# RoverWing-V1_5.net
KiCad netlist of a schematic drawn in EAGLE
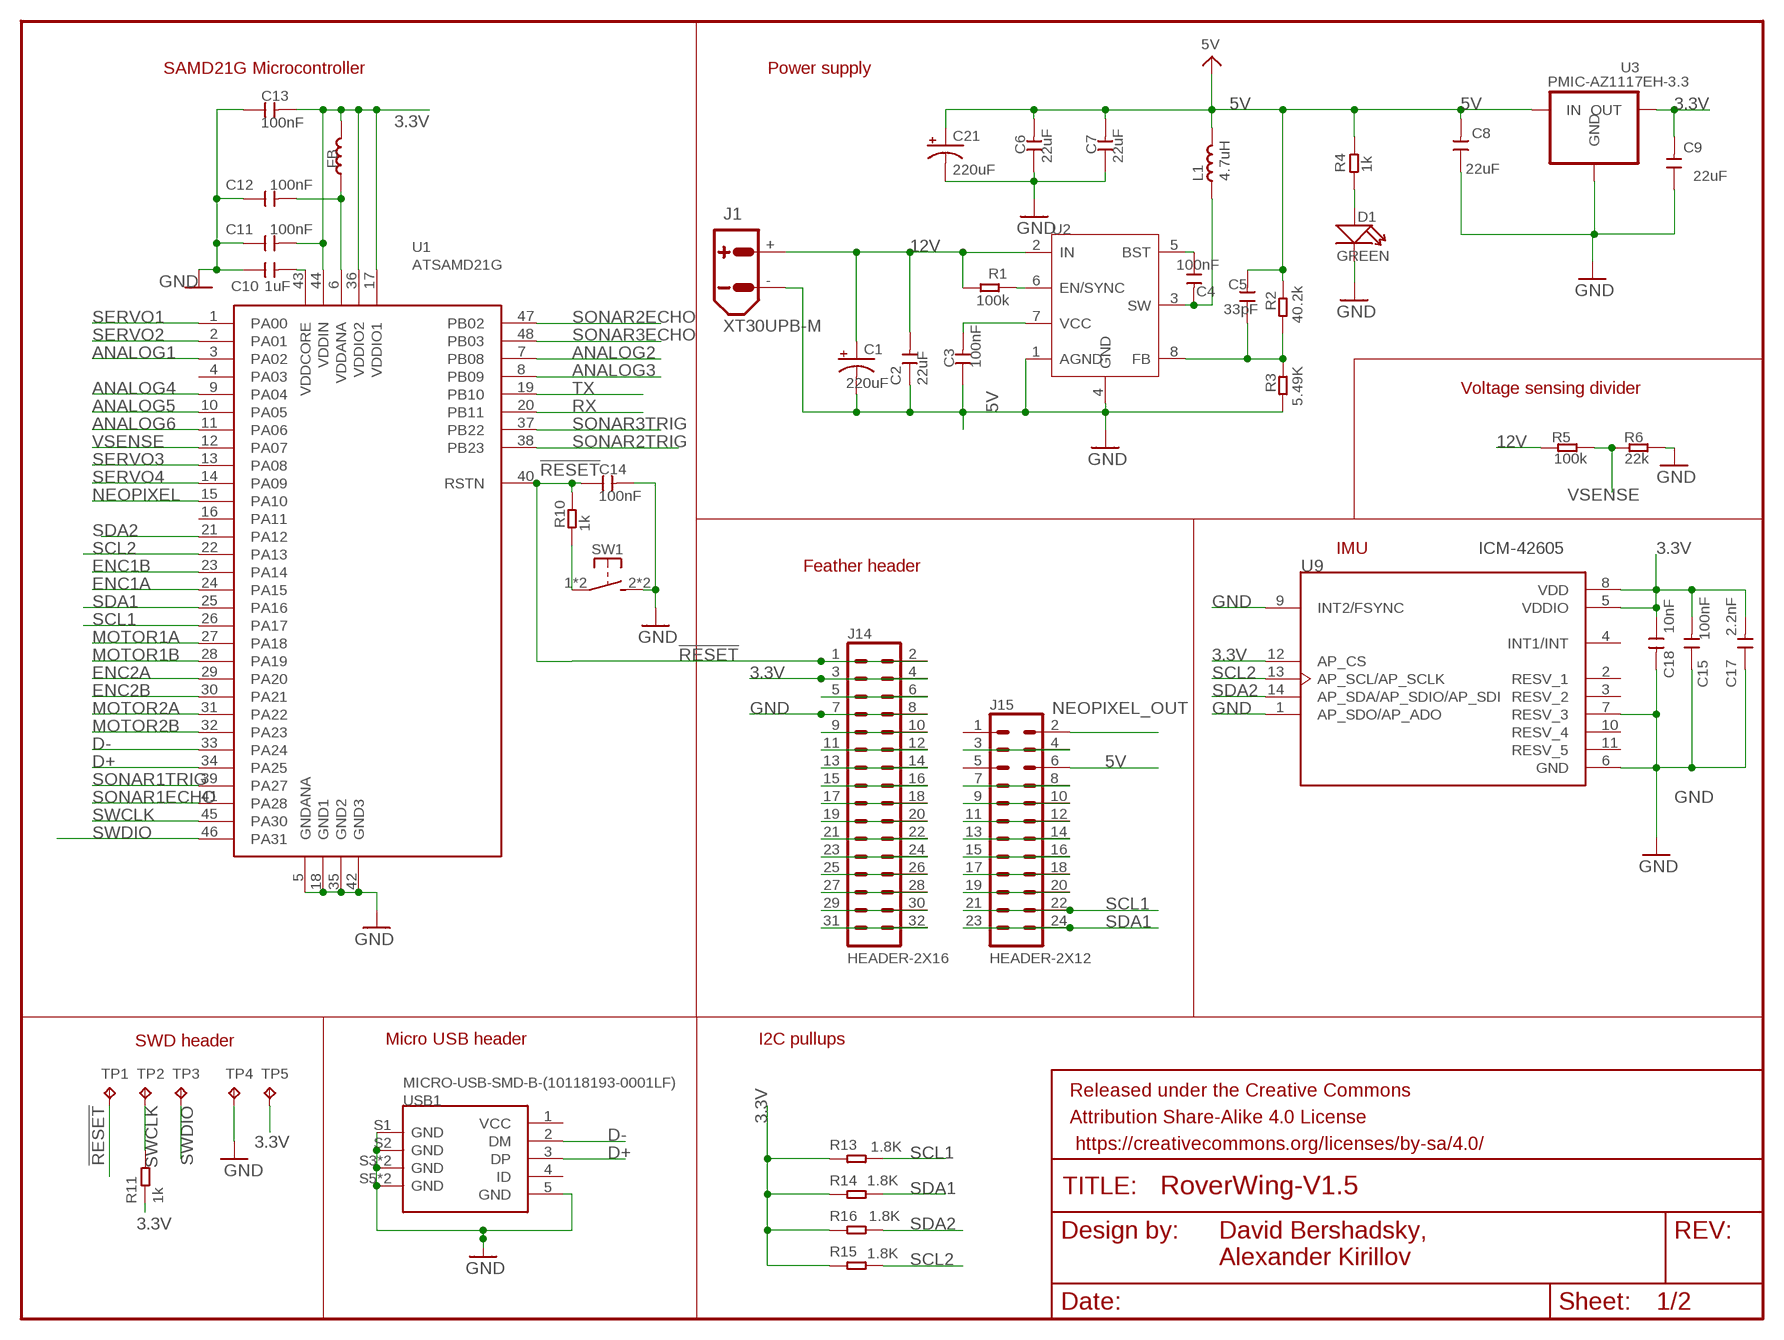
[diagram p0: schematic, sheet 1]
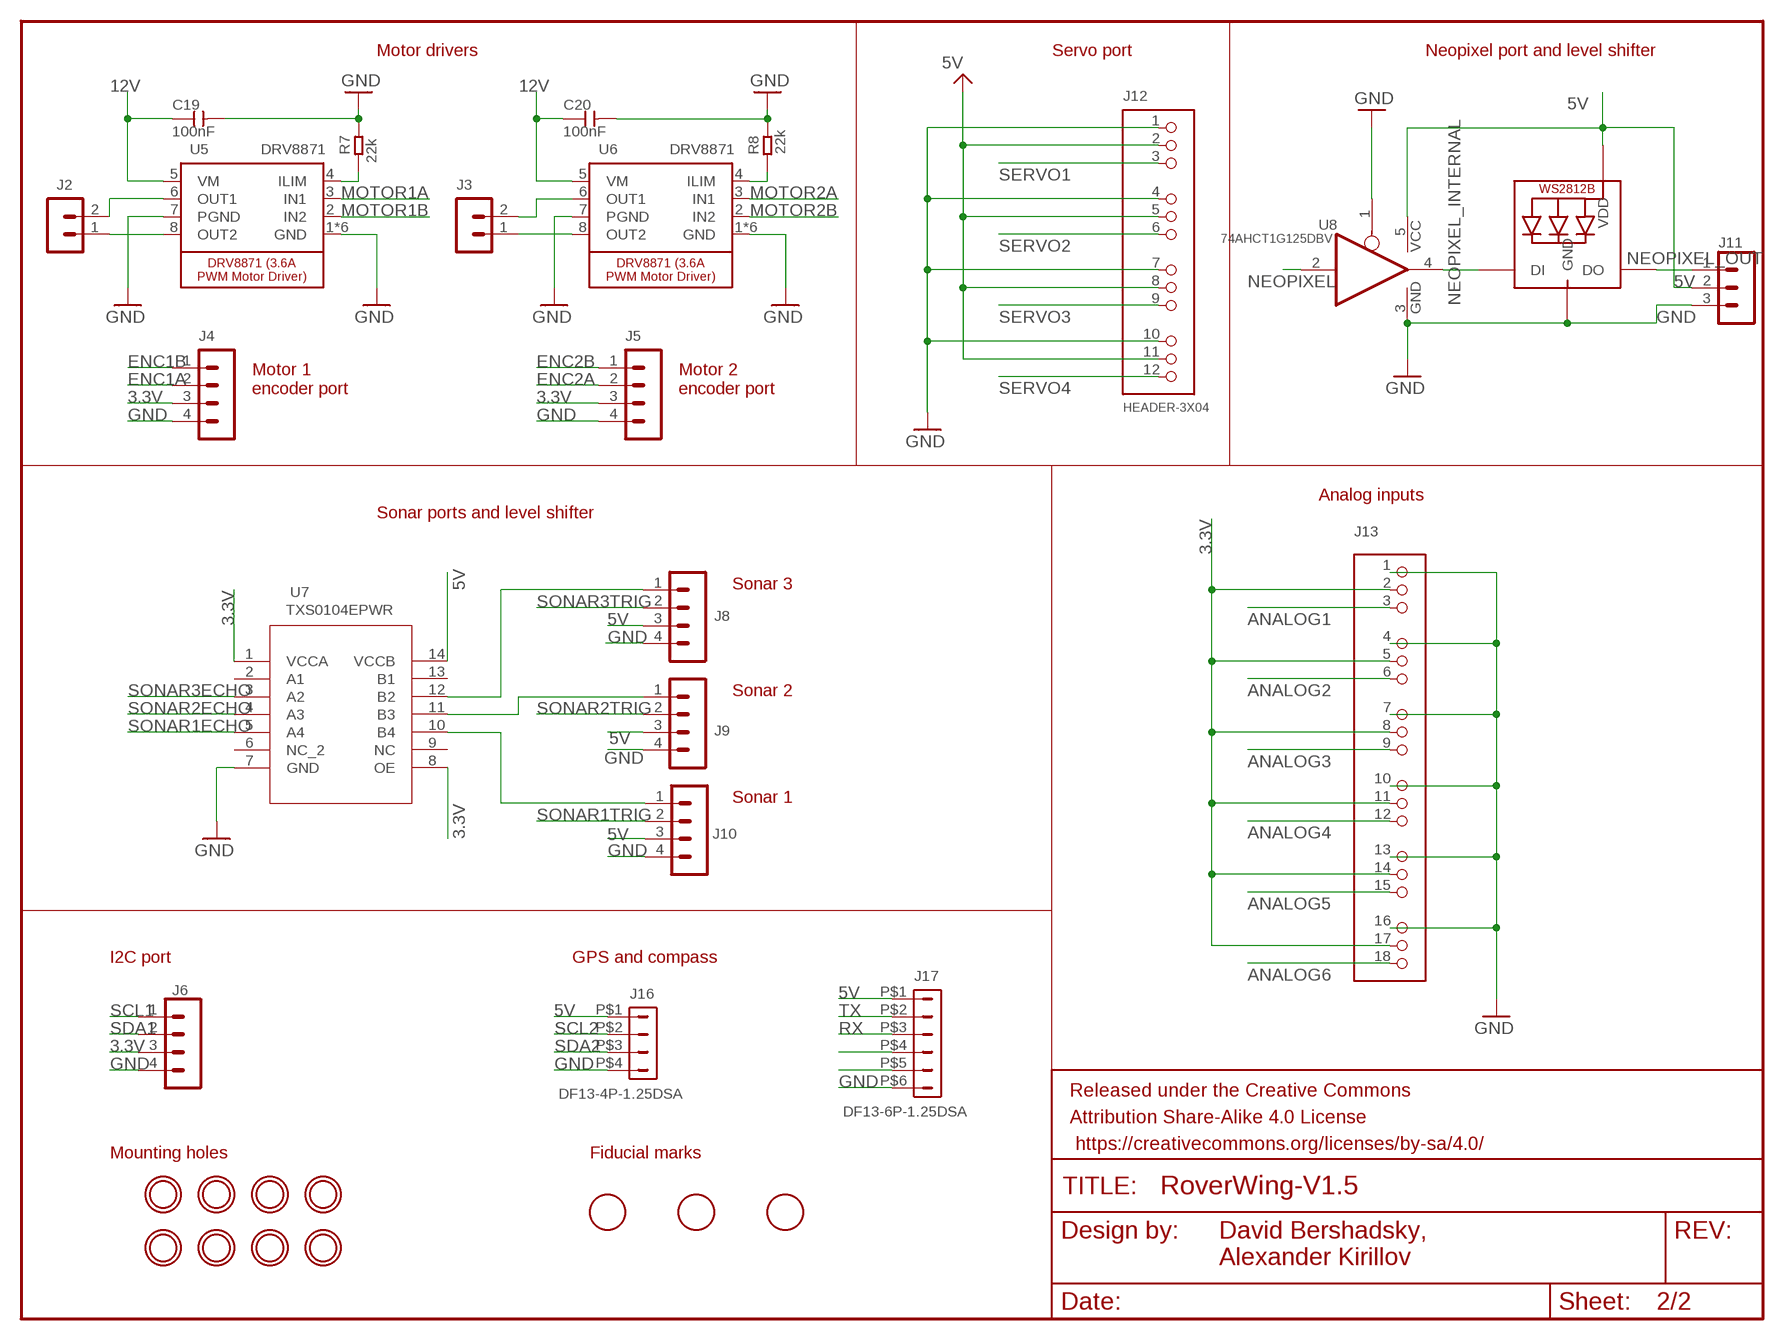
[diagram p1: schematic, sheet 2]

(export (version "E")
  (design (tool "Eeschema 10.0.6"))
  (components
    (comp (ref "C19")
      (value "100nF")
      (footprint "eagle-import:0805")
      (libsource (lib "eagle-import") (part "CAP-CERAMIC-SMD0805"))
    )
    (comp (ref "C20")
      (value "100nF")
      (footprint "eagle-import:0805")
      (libsource (lib "eagle-import") (part "CAP-CERAMIC-SMD0805"))
    )
    (comp (ref "D2")
      (value "WS2812B3535")
      (footprint "eagle-import:LED3535")
      (fields (field (name "MANUFACTURER") "Worldsemi") (field (name "PARTNO") "WS2812B-3535 "))
      (libsource (lib "eagle-import") (part "WS2812B3535"))
    )
    (comp (ref "FRAME1")
      (value "FRAME-LETTERNO_PACKAGE")
      (footprint "eagle-import:DUMMY")
      (libsource (lib "eagle-import") (part "FRAME-LETTERNO_PACKAGE"))
    )
    (comp (ref "J2")
      (value "HEADER-VH")
      (footprint "eagle-import:B2P-VH")
      (fields (field (name "PARTNO") "B2P-VH(LF)(SN)  "))
      (libsource (lib "eagle-import") (part "HEADER-VH"))
    )
    (comp (ref "J3")
      (value "HEADER-VH")
      (footprint "eagle-import:B2P-VH")
      (fields (field (name "PARTNO") "B2P-VH(LF)(SN)  "))
      (libsource (lib "eagle-import") (part "HEADER-VH"))
    )
    (comp (ref "J4")
      (value "HEADER-PH-4P")
      (footprint "eagle-import:B4B-PH-K")
      (fields (field (name "PARTNO") "B4B-PH-K-S(LF)(SN)"))
      (libsource (lib "eagle-import") (part "HEADER-PH-4P"))
    )
    (comp (ref "J5")
      (value "HEADER-PH-4P")
      (footprint "eagle-import:B4B-PH-K")
      (fields (field (name "PARTNO") "B4B-PH-K-S(LF)(SN)"))
      (libsource (lib "eagle-import") (part "HEADER-PH-4P"))
    )
    (comp (ref "J6")
      (value "HEADER-PH-4P")
      (footprint "eagle-import:B4B-PH-K")
      (fields (field (name "PARTNO") "B4B-PH-K-S(LF)(SN)"))
      (libsource (lib "eagle-import") (part "HEADER-PH-4P"))
    )
    (comp (ref "J8")
      (value "HEADER-PH-4P")
      (footprint "eagle-import:B4B-PH-K")
      (fields (field (name "PARTNO") "B4B-PH-K-S(LF)(SN)"))
      (libsource (lib "eagle-import") (part "HEADER-PH-4P"))
    )
    (comp (ref "J9")
      (value "HEADER-PH-4P")
      (footprint "eagle-import:B4B-PH-K")
      (fields (field (name "PARTNO") "B4B-PH-K-S(LF)(SN)"))
      (libsource (lib "eagle-import") (part "HEADER-PH-4P"))
    )
    (comp (ref "J10")
      (value "HEADER-PH-4P")
      (footprint "eagle-import:B4B-PH-K")
      (fields (field (name "PARTNO") "B4B-PH-K-S(LF)(SN)"))
      (libsource (lib "eagle-import") (part "HEADER-PH-4P"))
    )
    (comp (ref "J11")
      (value "HEADER-PH-3P")
      (footprint "eagle-import:B3B-PH-K")
      (fields (field (name "PARTNO") "B3B-PH-K-S(LF)(SN)"))
      (libsource (lib "eagle-import") (part "HEADER-PH-3P"))
    )
    (comp (ref "J12")
      (value "HEADER-3X04")
      (footprint "eagle-import:3X04")
      (libsource (lib "eagle-import") (part "HEADER-3X04"))
    )
    (comp (ref "J13")
      (value "HEADER-3X06\"")
      (footprint "eagle-import:3X06")
      (libsource (lib "eagle-import") (part "HEADER-3X06{dblquote}"))
    )
    (comp (ref "J16")
      (value "DF13-4P-1.25DSA")
      (footprint "eagle-import:DF13-4P-1.25DSA")
      (libsource (lib "eagle-import") (part "DF13-4P-1.25DSA"))
    )
    (comp (ref "J17")
      (value "DF13-6P-1.25DSA")
      (footprint "eagle-import:DF13-6P-1.25DSA")
      (libsource (lib "eagle-import") (part "DF13-6P-1.25DSA"))
    )
    (comp (ref "R7")
      (value "22k")
      (footprint "eagle-import:0805")
      (libsource (lib "eagle-import") (part "RES-SMD-0805"))
    )
    (comp (ref "R8")
      (value "22k")
      (footprint "eagle-import:0805")
      (libsource (lib "eagle-import") (part "RES-SMD-0805"))
    )
    (comp (ref "U$3")
      (value "MOUNTINGHOLE3.0_NPH")
      (footprint "eagle-import:MOUNTINGHOLE_3.0_NPH")
      (libsource (lib "eagle-import") (part "MOUNTINGHOLE3.0_NPH"))
    )
    (comp (ref "U$4")
      (value "MOUNTINGHOLE3.0_NPH")
      (footprint "eagle-import:MOUNTINGHOLE_3.0_NPH")
      (libsource (lib "eagle-import") (part "MOUNTINGHOLE3.0_NPH"))
    )
    (comp (ref "U$11")
      (value "FIDUCIAL")
      (footprint "eagle-import:FIDUCIAL_1MM")
      (libsource (lib "eagle-import") (part "FIDUCIAL"))
    )
    (comp (ref "U$13")
      (value "FIDUCIAL")
      (footprint "eagle-import:FIDUCIAL_1MM")
      (libsource (lib "eagle-import") (part "FIDUCIAL"))
    )
    (comp (ref "U$14")
      (value "MOUNTINGHOLE3.0_NPH")
      (footprint "eagle-import:MOUNTINGHOLE_3.0_NPH")
      (libsource (lib "eagle-import") (part "MOUNTINGHOLE3.0_NPH"))
    )
    (comp (ref "U$15")
      (value "MOUNTINGHOLE3.0_NPH")
      (footprint "eagle-import:MOUNTINGHOLE_3.0_NPH")
      (libsource (lib "eagle-import") (part "MOUNTINGHOLE3.0_NPH"))
    )
    (comp (ref "U$17")
      (value "FIDUCIAL")
      (footprint "eagle-import:FIDUCIAL_1MM")
      (libsource (lib "eagle-import") (part "FIDUCIAL"))
    )
    (comp (ref "U$24")
      (value "MOUNTINGHOLE3.0_NPH")
      (footprint "eagle-import:MOUNTINGHOLE_3.0_NPH")
      (libsource (lib "eagle-import") (part "MOUNTINGHOLE3.0_NPH"))
    )
    (comp (ref "U$25")
      (value "MOUNTINGHOLE3.0_NPH")
      (footprint "eagle-import:MOUNTINGHOLE_3.0_NPH")
      (libsource (lib "eagle-import") (part "MOUNTINGHOLE3.0_NPH"))
    )
    (comp (ref "U$26")
      (value "MOUNTINGHOLE3.0_NPH")
      (footprint "eagle-import:MOUNTINGHOLE_3.0_NPH")
      (libsource (lib "eagle-import") (part "MOUNTINGHOLE3.0_NPH"))
    )
    (comp (ref "U$27")
      (value "MOUNTINGHOLE3.0_NPH")
      (footprint "eagle-import:MOUNTINGHOLE_3.0_NPH")
      (libsource (lib "eagle-import") (part "MOUNTINGHOLE3.0_NPH"))
    )
    (comp (ref "U5")
      (value "DRV8871")
      (footprint "eagle-import:HSOP8")
      (fields (field (name "MANUFACTURER") "TEXAS INSTRUMENTS") (field (name "PARTNO") "DRV8871DDAR"))
      (libsource (lib "eagle-import") (part "DRV8871"))
    )
    (comp (ref "U6")
      (value "DRV8871")
      (footprint "eagle-import:HSOP8")
      (fields (field (name "MANUFACTURER") "TEXAS INSTRUMENTS") (field (name "PARTNO") "DRV8871DDAR"))
      (libsource (lib "eagle-import") (part "DRV8871"))
    )
    (comp (ref "U7")
      (value "TXS0104EPWR")
      (footprint "eagle-import:PW14")
      (fields (field (name "MANUFACTURER") "Texas Instruments"))
      (libsource (lib "eagle-import") (part "TXS0104EPWR"))
    )
    (comp (ref "U8")
      (value "74AHCT1G125DBV")
      (footprint "eagle-import:SOT23-5")
      (fields (field (name "PARTNO") "SN74AHCT1G125DBVR"))
      (libsource (lib "eagle-import") (part "741G125DBVAHCT"))
    )
    (comp (ref "C1")
      (value "220uF")
      (footprint "eagle-import:CAP-8X10.5")
      (libsource (lib "eagle-import") (part "CAP-POL-SMD-8X10.5"))
    )
    (comp (ref "C2")
      (value "22uF")
      (footprint "eagle-import:0805")
      (libsource (lib "eagle-import") (part "CAP-CERAMIC-SMD0805"))
    )
    (comp (ref "C3")
      (value "100nF")
      (footprint "eagle-import:0805")
      (libsource (lib "eagle-import") (part "CAP-CERAMIC-SMD0805"))
    )
    (comp (ref "C4")
      (value "100nF")
      (footprint "eagle-import:0805")
      (libsource (lib "eagle-import") (part "CAP-CERAMIC-SMD0805"))
    )
    (comp (ref "C5")
      (value "33pF")
      (footprint "eagle-import:0805")
      (libsource (lib "eagle-import") (part "CAP-CERAMIC-SMD0805"))
    )
    (comp (ref "C6")
      (value "22uF")
      (footprint "eagle-import:0805")
      (libsource (lib "eagle-import") (part "CAP-CERAMIC-SMD0805"))
    )
    (comp (ref "C7")
      (value "22uF")
      (footprint "eagle-import:0805")
      (libsource (lib "eagle-import") (part "CAP-CERAMIC-SMD0805"))
    )
    (comp (ref "C8")
      (value "22uF")
      (footprint "eagle-import:0805")
      (libsource (lib "eagle-import") (part "CAP-CERAMIC-SMD0805"))
    )
    (comp (ref "C9")
      (value "22uF")
      (footprint "eagle-import:0805")
      (libsource (lib "eagle-import") (part "CAP-CERAMIC-SMD0805"))
    )
    (comp (ref "C10")
      (value "1uF")
      (footprint "eagle-import:0805")
      (libsource (lib "eagle-import") (part "CAP-CERAMIC-SMD0805"))
    )
    (comp (ref "C11")
      (value "100nF")
      (footprint "eagle-import:0805")
      (libsource (lib "eagle-import") (part "CAP-CERAMIC-SMD0805"))
    )
    (comp (ref "C12")
      (value "100nF")
      (footprint "eagle-import:0805")
      (libsource (lib "eagle-import") (part "CAP-CERAMIC-SMD0805"))
    )
    (comp (ref "C13")
      (value "100nF")
      (footprint "eagle-import:0805")
      (libsource (lib "eagle-import") (part "CAP-CERAMIC-SMD0805"))
    )
    (comp (ref "C14")
      (value "100nF")
      (footprint "eagle-import:0805")
      (libsource (lib "eagle-import") (part "CAP-CERAMIC-SMD0805"))
    )
    (comp (ref "C15")
      (value "100nF")
      (footprint "eagle-import:0805")
      (libsource (lib "eagle-import") (part "CAP-CERAMIC-SMD0805"))
    )
    (comp (ref "C17")
      (value "2.2nF")
      (footprint "eagle-import:0805")
      (libsource (lib "eagle-import") (part "CAP-CERAMIC-SMD0805"))
    )
    (comp (ref "C18")
      (value "10nF")
      (footprint "eagle-import:0805")
      (libsource (lib "eagle-import") (part "CAP-CERAMIC-SMD0805"))
    )
    (comp (ref "C21")
      (value "220uF")
      (footprint "eagle-import:CAP-6.3X5.4")
      (fields (field (name "PARTNO") "CS1E470M-CRE54 "))
      (libsource (lib "eagle-import") (part "CAP-POL-SMD-6.3X5.4"))
    )
    (comp (ref "D1")
      (value "GREEN")
      (footprint "eagle-import:LED-0805")
      (libsource (lib "eagle-import") (part "SMD-LED-0805"))
    )
    (comp (ref "FB")
      (value "330R-1500MA")
      (footprint "eagle-import:0805")
      (fields (field (name "PARTNO") "BLM21PG331SN1D"))
      (libsource (lib "eagle-import") (part "SMD-FERRITE-BEAD-330R-1500MA(0805)"))
    )
    (comp (ref "FRAME2")
      (value "FRAME-LETTERNO_PACKAGE")
      (footprint "eagle-import:DUMMY")
      (libsource (lib "eagle-import") (part "FRAME-LETTERNO_PACKAGE"))
    )
    (comp (ref "J1")
      (value "XT30UPB-M")
      (footprint "eagle-import:XT30UPB-M")
      (libsource (lib "eagle-import") (part "XT30UPB-M"))
    )
    (comp (ref "J14")
      (value "HEADER-2X16")
      (footprint "eagle-import:2X16")
      (libsource (lib "eagle-import") (part "HEADER-2X16"))
    )
    (comp (ref "J15")
      (value "HEADER-2X12")
      (footprint "eagle-import:2X12")
      (libsource (lib "eagle-import") (part "HEADER-2X12"))
    )
    (comp (ref "L1")
      (value "4.7uH")
      (footprint "eagle-import:IND_TDK_7.1X6.5")
      (fields (field (name "MANUFACTURER") "TDK") (field (name "PARTNO") "SPM6530T-4R7M "))
      (libsource (lib "eagle-import") (part "IND-TDK-SPM6530T"))
    )
    (comp (ref "R1")
      (value "100k")
      (footprint "eagle-import:0805")
      (libsource (lib "eagle-import") (part "RES-SMD-0805"))
    )
    (comp (ref "R2")
      (value "40.2k")
      (footprint "eagle-import:0805")
      (libsource (lib "eagle-import") (part "RES-SMD-0805"))
    )
    (comp (ref "R3")
      (value "5.49K")
      (footprint "eagle-import:0805")
      (libsource (lib "eagle-import") (part "RES-SMD-0805"))
    )
    (comp (ref "R4")
      (value "1k")
      (footprint "eagle-import:0805")
      (libsource (lib "eagle-import") (part "RES-SMD-0805"))
    )
    (comp (ref "R5")
      (value "100k")
      (footprint "eagle-import:0805")
      (libsource (lib "eagle-import") (part "RES-SMD-0805"))
    )
    (comp (ref "R6")
      (value "22k")
      (footprint "eagle-import:0805")
      (libsource (lib "eagle-import") (part "RES-SMD-0805"))
    )
    (comp (ref "R10")
      (value "1k")
      (footprint "eagle-import:0805")
      (libsource (lib "eagle-import") (part "RES-SMD-0805"))
    )
    (comp (ref "R11")
      (value "1k")
      (footprint "eagle-import:0805")
      (libsource (lib "eagle-import") (part "RES-SMD-0805"))
    )
    (comp (ref "R13")
      (value "1.8K")
      (footprint "eagle-import:R0603")
      (fields (field (name "MPN") "RC0603FR-071K8L"))
      (libsource (lib "eagle-import") (part "SMD-RES-1.8K-1%-1/10W(0603)"))
    )
    (comp (ref "R14")
      (value "1.8K")
      (footprint "eagle-import:R0603")
      (fields (field (name "MPN") "RC0603FR-071K8L"))
      (libsource (lib "eagle-import") (part "SMD-RES-1.8K-1%-1/10W(0603)"))
    )
    (comp (ref "R15")
      (value "1.8K")
      (footprint "eagle-import:R0603")
      (fields (field (name "MPN") "RC0603FR-071K8L"))
      (libsource (lib "eagle-import") (part "SMD-RES-1.8K-1%-1/10W(0603)"))
    )
    (comp (ref "R16")
      (value "1.8K")
      (footprint "eagle-import:R0603")
      (fields (field (name "MPN") "RC0603FR-071K8L"))
      (libsource (lib "eagle-import") (part "SMD-RES-1.8K-1%-1/10W(0603)"))
    )
    (comp (ref "SW1")
      (value "SW-TACTILE-4.5X4.5_SMD")
      (footprint "eagle-import:TL3305")
      (fields (field (name "MANUFACTURER") "BRIGHT") (field (name "PARTNO") "TSA453G38-250 "))
      (libsource (lib "eagle-import") (part "SW-TACTILE-4.5X4.5_SMD"))
    )
    (comp (ref "TP1")
      (value "TPTP15R")
      (footprint "eagle-import:TP15R")
      (libsource (lib "eagle-import") (part "TPTP15R"))
    )
    (comp (ref "TP2")
      (value "TPTP15R")
      (footprint "eagle-import:TP15R")
      (libsource (lib "eagle-import") (part "TPTP15R"))
    )
    (comp (ref "TP3")
      (value "TPTP15R")
      (footprint "eagle-import:TP15R")
      (libsource (lib "eagle-import") (part "TPTP15R"))
    )
    (comp (ref "TP4")
      (value "TPTP15R")
      (footprint "eagle-import:TP15R")
      (libsource (lib "eagle-import") (part "TPTP15R"))
    )
    (comp (ref "TP5")
      (value "TPTP15R")
      (footprint "eagle-import:TP15R")
      (libsource (lib "eagle-import") (part "TPTP15R"))
    )
    (comp (ref "U1")
      (value "ATSAMD21G")
      (footprint "eagle-import:TQFP-48-EDITED")
      (fields (field (name "MANUFACTURER") "Microchip Technology") (field (name "PARTNO") "ATSAMD21G18A-AU"))
      (libsource (lib "eagle-import") (part "ATSAMD21G"))
    )
    (comp (ref "U2")
      (value "MP2225")
      (footprint "eagle-import:SOT-23-8")
      (fields (field (name "MANUFACTURER") "Monolithic Power Systems") (field (name "PARTNO") "MP2225GJ"))
      (libsource (lib "eagle-import") (part "PMIC-MP2225"))
    )
    (comp (ref "U3")
      (value "PMIC-AZ1117EH-3.3")
      (footprint "eagle-import:SOT223")
      (fields (field (name "PARTNO") "AZ1117EH-3.3TRG1"))
      (libsource (lib "eagle-import") (part "PMIC-AZ1117EH-3.3"))
    )
    (comp (ref "U9")
      (value "ICM-42605")
      (footprint "eagle-import:PQFN50P300X250X97-14N")
      (fields (field (name "DIGI-KEY_PART_NUMBER") "1428-1152-1-ND") (field (name "MF") "TDK InvenSense"))
      (libsource (lib "eagle-import") (part "ICM-42605"))
    )
    (comp (ref "USB1")
      (value "MICRO-USB-SMD-B-(10118193-0001LF)")
      (footprint "eagle-import:MICRO-USB5+6P-SMD-0.65-B")
      (fields (field (name "MANUFACTURER") "Amphenol ICC") (field (name "PARTNO") "10118193-0001LF"))
      (libsource (lib "eagle-import") (part "MICRO-USB-SMD-B-(10118193-0001LF)"))
    )
  )
  (nets
    (net (code "1") (name "3.3V") (class "Default")
      (node (ref "C11") (pin "2") (pinfunction "2_2") (pintype "passive"))
      (node (ref "C13") (pin "2") (pinfunction "2_2") (pintype "passive"))
      (node (ref "C15") (pin "2") (pinfunction "2_2") (pintype "passive"))
      (node (ref "C17") (pin "2") (pinfunction "2_2") (pintype "passive"))
      (node (ref "C18") (pin "1") (pinfunction "1_1") (pintype "passive"))
      (node (ref "C9") (pin "2") (pinfunction "2_2") (pintype "passive"))
      (node (ref "FB") (pin "2") (pinfunction "2_2") (pintype "passive"))
      (node (ref "J13") (pin "11") (pinfunction "11_11") (pintype "passive"))
      (node (ref "J13") (pin "14") (pinfunction "14_14") (pintype "passive"))
      (node (ref "J13") (pin "17") (pinfunction "17_17") (pintype "passive"))
      (node (ref "J13") (pin "2") (pinfunction "2_2") (pintype "passive"))
      (node (ref "J13") (pin "5") (pinfunction "5_5") (pintype "passive"))
      (node (ref "J13") (pin "8") (pinfunction "8_8") (pintype "passive"))
      (node (ref "J14") (pin "3") (pinfunction "3_3") (pintype "passive"))
      (node (ref "J14") (pin "4") (pinfunction "4_4") (pintype "passive"))
      (node (ref "J4") (pin "3") (pinfunction "3_3") (pintype "passive"))
      (node (ref "J5") (pin "3") (pinfunction "3_3") (pintype "passive"))
      (node (ref "J6") (pin "3") (pinfunction "3_3") (pintype "passive"))
      (node (ref "R11") (pin "1") (pinfunction "1_1") (pintype "passive"))
      (node (ref "R13") (pin "1") (pinfunction "1_1") (pintype "passive"))
      (node (ref "R14") (pin "1") (pinfunction "1_1") (pintype "passive"))
      (node (ref "R15") (pin "1") (pinfunction "1_1") (pintype "passive"))
      (node (ref "R16") (pin "1") (pinfunction "1_1") (pintype "passive"))
      (node (ref "TP5") (pin "TP") (pinfunction "TP_TP") (pintype "input"))
      (node (ref "U1") (pin "17") (pinfunction "VDDIO1_17") (pintype "power_in"))
      (node (ref "U1") (pin "36") (pinfunction "VDDIO2_36") (pintype "power_in"))
      (node (ref "U1") (pin "44") (pinfunction "VDDIN_44") (pintype "power_in"))
      (node (ref "U3") (pin "2") (pinfunction "OUT_2") (pintype "output"))
      (node (ref "U3") (pin "4") (pinfunction "OUT_4") (pintype "output"))
      (node (ref "U7") (pin "1") (pinfunction "VCCA_1") (pintype "power_in"))
      (node (ref "U7") (pin "8") (pinfunction "OE_8") (pintype "output"))
      (node (ref "U9") (pin "12") (pinfunction "AP_CS_12") (pintype "input"))
      (node (ref "U9") (pin "5") (pinfunction "VDDIO_5") (pintype "power_in"))
      (node (ref "U9") (pin "8") (pinfunction "VDD_8") (pintype "power_in"))
    )
    (net (code "2") (name "5V") (class "Default")
      (node (ref "C21") (pin "+") (pinfunction "+_+") (pintype "passive"))
      (node (ref "C5") (pin "2") (pinfunction "2_2") (pintype "passive"))
      (node (ref "C6") (pin "2") (pinfunction "2_2") (pintype "passive"))
      (node (ref "C7") (pin "2") (pinfunction "2_2") (pintype "passive"))
      (node (ref "C8") (pin "2") (pinfunction "2_2") (pintype "passive"))
      (node (ref "D2") (pin "3") (pinfunction "VDD_3") (pintype "power_in"))
      (node (ref "J10") (pin "3") (pinfunction "3_3") (pintype "passive"))
      (node (ref "J11") (pin "2") (pinfunction "2_2") (pintype "passive"))
      (node (ref "J12") (pin "11") (pinfunction "11_11") (pintype "passive"))
      (node (ref "J12") (pin "2") (pinfunction "2_2") (pintype "passive"))
      (node (ref "J12") (pin "5") (pinfunction "5_5") (pintype "passive"))
      (node (ref "J12") (pin "8") (pinfunction "8_8") (pintype "passive"))
      (node (ref "J15") (pin "6") (pinfunction "6_6") (pintype "passive"))
      (node (ref "J16") (pin "P$1") (pinfunction "1_P$1") (pintype "passive"))
      (node (ref "J17") (pin "P$1") (pinfunction "1_P$1") (pintype "passive"))
      (node (ref "J8") (pin "3") (pinfunction "3_3") (pintype "passive"))
      (node (ref "J9") (pin "3") (pinfunction "3_3") (pintype "passive"))
      (node (ref "L1") (pin "2") (pinfunction "2_2") (pintype "passive"))
      (node (ref "R2") (pin "1") (pinfunction "1_1") (pintype "passive"))
      (node (ref "R4") (pin "2") (pinfunction "2_2") (pintype "passive"))
      (node (ref "U3") (pin "3") (pinfunction "IN_3") (pintype "input"))
      (node (ref "U7") (pin "14") (pinfunction "VCCB_14") (pintype "power_in"))
      (node (ref "U8") (pin "5") (pinfunction "VCC_5") (pintype "power_in"))
    )
    (net (code "3") (name "12V") (class "Default")
      (node (ref "C1") (pin "+") (pinfunction "+_+") (pintype "passive"))
      (node (ref "C19") (pin "1") (pinfunction "1_1") (pintype "passive"))
      (node (ref "C2") (pin "2") (pinfunction "2_2") (pintype "passive"))
      (node (ref "C20") (pin "1") (pinfunction "1_1") (pintype "passive"))
      (node (ref "J1") (pin "+") (pinfunction "+_+") (pintype "power_in"))
      (node (ref "R1") (pin "2") (pinfunction "2_2") (pintype "passive"))
      (node (ref "R5") (pin "2") (pinfunction "2_2") (pintype "passive"))
      (node (ref "U2") (pin "2") (pinfunction "IN_2") (pintype "bidirectional"))
      (node (ref "U5") (pin "5") (pinfunction "VM_5") (pintype "power_in"))
      (node (ref "U6") (pin "5") (pinfunction "VM_5") (pintype "power_in"))
    )
    (net (code "4") (name "ANALOG1") (class "Default")
      (node (ref "J13") (pin "3") (pinfunction "3_3") (pintype "passive"))
      (node (ref "U1") (pin "3") (pinfunction "PA02_3") (pintype "bidirectional"))
    )
    (net (code "5") (name "ANALOG2") (class "Default")
      (node (ref "J13") (pin "6") (pinfunction "6_6") (pintype "passive"))
      (node (ref "U1") (pin "7") (pinfunction "PB08_7") (pintype "bidirectional"))
    )
    (net (code "6") (name "ANALOG3") (class "Default")
      (node (ref "J13") (pin "9") (pinfunction "9_9") (pintype "passive"))
      (node (ref "U1") (pin "8") (pinfunction "PB09_8") (pintype "bidirectional"))
    )
    (net (code "7") (name "ANALOG4") (class "Default")
      (node (ref "J13") (pin "12") (pinfunction "12_12") (pintype "passive"))
      (node (ref "U1") (pin "9") (pinfunction "PA04_9") (pintype "bidirectional"))
    )
    (net (code "8") (name "ANALOG5") (class "Default")
      (node (ref "J13") (pin "15") (pinfunction "15_15") (pintype "passive"))
      (node (ref "U1") (pin "10") (pinfunction "PA05_10") (pintype "bidirectional"))
    )
    (net (code "9") (name "ANALOG6") (class "Default")
      (node (ref "J13") (pin "18") (pinfunction "18_18") (pintype "passive"))
      (node (ref "U1") (pin "11") (pinfunction "PA06_11") (pintype "bidirectional"))
    )
    (net (code "10") (name "D+") (class "Default")
      (node (ref "U1") (pin "34") (pinfunction "PA25_34") (pintype "bidirectional"))
      (node (ref "USB1") (pin "3") (pinfunction "DP_3") (pintype "bidirectional"))
    )
    (net (code "11") (name "D-") (class "Default")
      (node (ref "U1") (pin "33") (pinfunction "PA24_33") (pintype "bidirectional"))
      (node (ref "USB1") (pin "2") (pinfunction "DM_2") (pintype "bidirectional"))
    )
    (net (code "12") (name "ENC1A") (class "Default")
      (node (ref "J4") (pin "2") (pinfunction "2_2") (pintype "passive"))
      (node (ref "U1") (pin "24") (pinfunction "PA15_24") (pintype "bidirectional"))
    )
    (net (code "13") (name "ENC1B") (class "Default")
      (node (ref "J4") (pin "1") (pinfunction "1_1") (pintype "passive"))
      (node (ref "U1") (pin "23") (pinfunction "PA14_23") (pintype "bidirectional"))
    )
    (net (code "14") (name "ENC2A") (class "Default")
      (node (ref "J5") (pin "2") (pinfunction "2_2") (pintype "passive"))
      (node (ref "U1") (pin "29") (pinfunction "PA20_29") (pintype "bidirectional"))
    )
    (net (code "15") (name "ENC2B") (class "Default")
      (node (ref "J5") (pin "1") (pinfunction "1_1") (pintype "passive"))
      (node (ref "U1") (pin "30") (pinfunction "PA21_30") (pintype "bidirectional"))
    )
    (net (code "16") (name "GND") (class "Default")
      (node (ref "C1") (pin "-") (pinfunction "-_-") (pintype "passive"))
      (node (ref "C10") (pin "1") (pinfunction "1_1") (pintype "passive"))
      (node (ref "C11") (pin "1") (pinfunction "1_1") (pintype "passive"))
      (node (ref "C12") (pin "1") (pinfunction "1_1") (pintype "passive"))
      (node (ref "C13") (pin "1") (pinfunction "1_1") (pintype "passive"))
      (node (ref "C14") (pin "2") (pinfunction "2_2") (pintype "passive"))
      (node (ref "C15") (pin "1") (pinfunction "1_1") (pintype "passive"))
      (node (ref "C17") (pin "1") (pinfunction "1_1") (pintype "passive"))
      (node (ref "C18") (pin "2") (pinfunction "2_2") (pintype "passive"))
      (node (ref "C19") (pin "2") (pinfunction "2_2") (pintype "passive"))
      (node (ref "C2") (pin "1") (pinfunction "1_1") (pintype "passive"))
      (node (ref "C20") (pin "2") (pinfunction "2_2") (pintype "passive"))
      (node (ref "C21") (pin "-") (pinfunction "-_-") (pintype "passive"))
      (node (ref "C3") (pin "1") (pinfunction "1_1") (pintype "passive"))
      (node (ref "C6") (pin "1") (pinfunction "1_1") (pintype "passive"))
      (node (ref "C7") (pin "1") (pinfunction "1_1") (pintype "passive"))
      (node (ref "C8") (pin "1") (pinfunction "1_1") (pintype "passive"))
      (node (ref "C9") (pin "1") (pinfunction "1_1") (pintype "passive"))
      (node (ref "D1") (pin "-") (pinfunction "-_-") (pintype "passive"))
      (node (ref "D2") (pin "1") (pinfunction "GND_1") (pintype "power_in"))
      (node (ref "J1") (pin "-") (pinfunction "-_-") (pintype "power_in"))
      (node (ref "J10") (pin "4") (pinfunction "4_4") (pintype "passive"))
      (node (ref "J11") (pin "3") (pinfunction "3_3") (pintype "passive"))
      (node (ref "J12") (pin "1") (pinfunction "1_1") (pintype "passive"))
      (node (ref "J12") (pin "10") (pinfunction "10_10") (pintype "passive"))
      (node (ref "J12") (pin "4") (pinfunction "4_4") (pintype "passive"))
      (node (ref "J12") (pin "7") (pinfunction "7_7") (pintype "passive"))
      (node (ref "J13") (pin "1") (pinfunction "1_1") (pintype "passive"))
      (node (ref "J13") (pin "10") (pinfunction "10_10") (pintype "passive"))
      (node (ref "J13") (pin "13") (pinfunction "13_13") (pintype "passive"))
      (node (ref "J13") (pin "16") (pinfunction "16_16") (pintype "passive"))
      (node (ref "J13") (pin "4") (pinfunction "4_4") (pintype "passive"))
      (node (ref "J13") (pin "7") (pinfunction "7_7") (pintype "passive"))
      (node (ref "J14") (pin "7") (pinfunction "7_7") (pintype "passive"))
      (node (ref "J14") (pin "8") (pinfunction "8_8") (pintype "passive"))
      (node (ref "J16") (pin "P$4") (pinfunction "4_P$4") (pintype "passive"))
      (node (ref "J17") (pin "P$6") (pinfunction "6_P$6") (pintype "passive"))
      (node (ref "J4") (pin "4") (pinfunction "4_4") (pintype "passive"))
      (node (ref "J5") (pin "4") (pinfunction "4_4") (pintype "passive"))
      (node (ref "J6") (pin "4") (pinfunction "4_4") (pintype "passive"))
      (node (ref "J8") (pin "4") (pinfunction "4_4") (pintype "passive"))
      (node (ref "J9") (pin "4") (pinfunction "4_4") (pintype "passive"))
      (node (ref "R3") (pin "2") (pinfunction "2_2") (pintype "passive"))
      (node (ref "R6") (pin "2") (pinfunction "2_2") (pintype "passive"))
      (node (ref "R7") (pin "2") (pinfunction "2_2") (pintype "passive"))
      (node (ref "R8") (pin "2") (pinfunction "2_2") (pintype "passive"))
      (node (ref "SW1") (pin "2") (pinfunction "S1_2") (pintype "passive"))
      (node (ref "SW1") (pin "3") (pinfunction "S1_3") (pintype "passive"))
      (node (ref "TP4") (pin "TP") (pinfunction "TP_TP") (pintype "input"))
      (node (ref "U1") (pin "18") (pinfunction "GND1_18") (pintype "power_in"))
      (node (ref "U1") (pin "35") (pinfunction "GND2_35") (pintype "power_in"))
      (node (ref "U1") (pin "42") (pinfunction "GND3_42") (pintype "power_in"))
      (node (ref "U1") (pin "5") (pinfunction "GNDANA_5") (pintype "power_in"))
      (node (ref "U2") (pin "1") (pinfunction "AGND_1") (pintype "bidirectional"))
      (node (ref "U2") (pin "4") (pinfunction "GND_4") (pintype "bidirectional"))
      (node (ref "U3") (pin "1") (pinfunction "GND_1") (pintype "power_in"))
      (node (ref "U5") (pin "1") (pinfunction "GND_1") (pintype "power_in"))
      (node (ref "U5") (pin "7") (pinfunction "PGND_7") (pintype "power_in"))
      (node (ref "U5") (pin "GND") (pinfunction "GND_GND") (pintype "power_in"))
      (node (ref "U5") (pin "P$1") (pinfunction "GND_P$1") (pintype "power_in"))
      (node (ref "U5") (pin "P$2") (pinfunction "GND_P$2") (pintype "power_in"))
      (node (ref "U5") (pin "P$3") (pinfunction "GND_P$3") (pintype "power_in"))
      (node (ref "U5") (pin "P$4") (pinfunction "GND_P$4") (pintype "power_in"))
      (node (ref "U6") (pin "1") (pinfunction "GND_1") (pintype "power_in"))
      (node (ref "U6") (pin "7") (pinfunction "PGND_7") (pintype "power_in"))
      (node (ref "U6") (pin "GND") (pinfunction "GND_GND") (pintype "power_in"))
      (node (ref "U6") (pin "P$1") (pinfunction "GND_P$1") (pintype "power_in"))
      (node (ref "U6") (pin "P$2") (pinfunction "GND_P$2") (pintype "power_in"))
      (node (ref "U6") (pin "P$3") (pinfunction "GND_P$3") (pintype "power_in"))
      (node (ref "U6") (pin "P$4") (pinfunction "GND_P$4") (pintype "power_in"))
      (node (ref "U7") (pin "7") (pinfunction "GND_7") (pintype "power_in"))
      (node (ref "U8") (pin "1") (pinfunction "OE_1") (pintype "input"))
      (node (ref "U8") (pin "3") (pinfunction "GND_3") (pintype "power_in"))
      (node (ref "U9") (pin "1") (pinfunction "AP_SDO/AP_ADO_1") (pintype "output"))
      (node (ref "U9") (pin "6") (pinfunction "GND_6") (pintype "power_in"))
      (node (ref "U9") (pin "7") (pinfunction "RESV_3_7") (pintype "bidirectional"))
      (node (ref "U9") (pin "9") (pinfunction "INT2/FSYNC_9") (pintype "bidirectional"))
      (node (ref "USB1") (pin "5") (pinfunction "GND_5") (pintype "bidirectional"))
      (node (ref "USB1") (pin "S1") (pinfunction "GND_S1") (pintype "bidirectional"))
      (node (ref "USB1") (pin "S2") (pinfunction "GND_S2") (pintype "bidirectional"))
      (node (ref "USB1") (pin "S3") (pinfunction "GND_S3") (pintype "bidirectional"))
      (node (ref "USB1") (pin "S4") (pinfunction "GND_S4") (pintype "bidirectional"))
      (node (ref "USB1") (pin "S5") (pinfunction "GND_S5") (pintype "bidirectional"))
      (node (ref "USB1") (pin "S6") (pinfunction "GND_S6") (pintype "bidirectional"))
    )
    (net (code "17") (name "MOTOR1A") (class "Default")
      (node (ref "U1") (pin "27") (pinfunction "PA18_27") (pintype "bidirectional"))
      (node (ref "U5") (pin "3") (pinfunction "IN1_3") (pintype "input"))
    )
    (net (code "18") (name "MOTOR1B") (class "Default")
      (node (ref "U1") (pin "28") (pinfunction "PA19_28") (pintype "bidirectional"))
      (node (ref "U5") (pin "2") (pinfunction "IN2_2") (pintype "input"))
    )
    (net (code "19") (name "MOTOR2A") (class "Default")
      (node (ref "U1") (pin "31") (pinfunction "PA22_31") (pintype "bidirectional"))
      (node (ref "U6") (pin "3") (pinfunction "IN1_3") (pintype "input"))
    )
    (net (code "20") (name "MOTOR2B") (class "Default")
      (node (ref "U1") (pin "32") (pinfunction "PA23_32") (pintype "bidirectional"))
      (node (ref "U6") (pin "2") (pinfunction "IN2_2") (pintype "input"))
    )
    (net (code "21") (name "NEOPIXEL") (class "Default")
      (node (ref "U1") (pin "15") (pinfunction "PA10_15") (pintype "bidirectional"))
      (node (ref "U8") (pin "2") (pinfunction "I_2") (pintype "input"))
    )
    (net (code "22") (name "NEOPIXEL_INTERNAL") (class "Default")
      (node (ref "D2") (pin "2") (pinfunction "DI_2") (pintype "input"))
      (node (ref "U8") (pin "4") (pinfunction "O_4") (pintype "tri_state"))
    )
    (net (code "23") (name "NEOPIXEL_OUT") (class "Default")
      (node (ref "D2") (pin "4") (pinfunction "DO_4") (pintype "output"))
      (node (ref "J11") (pin "1") (pinfunction "1_1") (pintype "passive"))
      (node (ref "J15") (pin "2") (pinfunction "2_2") (pintype "passive"))
    )
    (net (code "24") (name "Net-(D1-Pad+)") (class "Default")
      (node (ref "D1") (pin "+") (pinfunction "+_+") (pintype "passive"))
      (node (ref "R4") (pin "1") (pinfunction "1_1") (pintype "passive"))
    )
    (net (code "25") (name "Net-(J14-Pad5)") (class "Default")
      (node (ref "J14") (pin "5") (pinfunction "5_5") (pintype "passive"))
      (node (ref "J14") (pin "6") (pinfunction "6_6") (pintype "passive"))
    )
    (net (code "26") (name "Net-(J14-Pad10)") (class "Default")
      (node (ref "J14") (pin "10") (pinfunction "10_10") (pintype "passive"))
      (node (ref "J14") (pin "9") (pinfunction "9_9") (pintype "passive"))
    )
    (net (code "27") (name "Net-(J14-Pad11)") (class "Default")
      (node (ref "J14") (pin "11") (pinfunction "11_11") (pintype "passive"))
      (node (ref "J14") (pin "12") (pinfunction "12_12") (pintype "passive"))
    )
    (net (code "28") (name "Net-(J14-Pad13)") (class "Default")
      (node (ref "J14") (pin "13") (pinfunction "13_13") (pintype "passive"))
      (node (ref "J14") (pin "14") (pinfunction "14_14") (pintype "passive"))
    )
    (net (code "29") (name "Net-(J14-Pad15)") (class "Default")
      (node (ref "J14") (pin "15") (pinfunction "15_15") (pintype "passive"))
      (node (ref "J14") (pin "16") (pinfunction "16_16") (pintype "passive"))
    )
    (net (code "30") (name "Net-(J14-Pad17)") (class "Default")
      (node (ref "J14") (pin "17") (pinfunction "17_17") (pintype "passive"))
      (node (ref "J14") (pin "18") (pinfunction "18_18") (pintype "passive"))
    )
    (net (code "31") (name "Net-(J14-Pad19)") (class "Default")
      (node (ref "J14") (pin "19") (pinfunction "19_19") (pintype "passive"))
      (node (ref "J14") (pin "20") (pinfunction "20_20") (pintype "passive"))
    )
    (net (code "32") (name "Net-(J14-Pad21)") (class "Default")
      (node (ref "J14") (pin "21") (pinfunction "21_21") (pintype "passive"))
      (node (ref "J14") (pin "22") (pinfunction "22_22") (pintype "passive"))
    )
    (net (code "33") (name "Net-(J14-Pad23)") (class "Default")
      (node (ref "J14") (pin "23") (pinfunction "23_23") (pintype "passive"))
      (node (ref "J14") (pin "24") (pinfunction "24_24") (pintype "passive"))
    )
    (net (code "34") (name "Net-(J14-Pad25)") (class "Default")
      (node (ref "J14") (pin "25") (pinfunction "25_25") (pintype "passive"))
      (node (ref "J14") (pin "26") (pinfunction "26_26") (pintype "passive"))
    )
    (net (code "35") (name "Net-(J14-Pad27)") (class "Default")
      (node (ref "J14") (pin "27") (pinfunction "27_27") (pintype "passive"))
      (node (ref "J14") (pin "28") (pinfunction "28_28") (pintype "passive"))
    )
    (net (code "36") (name "Net-(J14-Pad29)") (class "Default")
      (node (ref "J14") (pin "29") (pinfunction "29_29") (pintype "passive"))
      (node (ref "J14") (pin "30") (pinfunction "30_30") (pintype "passive"))
    )
    (net (code "37") (name "Net-(J14-Pad31)") (class "Default")
      (node (ref "J14") (pin "31") (pinfunction "31_31") (pintype "passive"))
      (node (ref "J14") (pin "32") (pinfunction "32_32") (pintype "passive"))
    )
    (net (code "38") (name "Net-(J15-Pad3)") (class "Default")
      (node (ref "J15") (pin "3") (pinfunction "3_3") (pintype "passive"))
      (node (ref "J15") (pin "4") (pinfunction "4_4") (pintype "passive"))
    )
    (net (code "39") (name "Net-(J15-Pad7)") (class "Default")
      (node (ref "J15") (pin "7") (pinfunction "7_7") (pintype "passive"))
      (node (ref "J15") (pin "8") (pinfunction "8_8") (pintype "passive"))
    )
    (net (code "40") (name "Net-(J15-Pad10)") (class "Default")
      (node (ref "J15") (pin "10") (pinfunction "10_10") (pintype "passive"))
      (node (ref "J15") (pin "9") (pinfunction "9_9") (pintype "passive"))
    )
    (net (code "41") (name "Net-(J15-Pad11)") (class "Default")
      (node (ref "J15") (pin "11") (pinfunction "11_11") (pintype "passive"))
      (node (ref "J15") (pin "12") (pinfunction "12_12") (pintype "passive"))
    )
    (net (code "42") (name "Net-(J15-Pad13)") (class "Default")
      (node (ref "J15") (pin "13") (pinfunction "13_13") (pintype "passive"))
      (node (ref "J15") (pin "14") (pinfunction "14_14") (pintype "passive"))
    )
    (net (code "43") (name "Net-(J15-Pad15)") (class "Default")
      (node (ref "J15") (pin "15") (pinfunction "15_15") (pintype "passive"))
      (node (ref "J15") (pin "16") (pinfunction "16_16") (pintype "passive"))
    )
    (net (code "44") (name "Net-(J15-Pad17)") (class "Default")
      (node (ref "J15") (pin "17") (pinfunction "17_17") (pintype "passive"))
      (node (ref "J15") (pin "18") (pinfunction "18_18") (pintype "passive"))
    )
    (net (code "45") (name "Net-(J15-Pad19)") (class "Default")
      (node (ref "J15") (pin "19") (pinfunction "19_19") (pintype "passive"))
      (node (ref "J15") (pin "20") (pinfunction "20_20") (pintype "passive"))
    )
    (net (code "46") (name "Net-(R10-Pad1)") (class "Default")
      (node (ref "R10") (pin "1") (pinfunction "1_1") (pintype "passive"))
      (node (ref "SW1") (pin "1") (pinfunction "P1_1") (pintype "passive"))
      (node (ref "SW1") (pin "4") (pinfunction "P1_4") (pintype "passive"))
    )
    (net (code "47") (name "Net-(U1-VDDANA)") (class "Default")
      (node (ref "C12") (pin "2") (pinfunction "2_2") (pintype "passive"))
      (node (ref "FB") (pin "1") (pinfunction "1_1") (pintype "passive"))
      (node (ref "U1") (pin "6") (pinfunction "VDDANA_6") (pintype "power_in"))
    )
    (net (code "48") (name "Net-(U1-VDDCORE)") (class "Default")
      (node (ref "C10") (pin "2") (pinfunction "2_2") (pintype "passive"))
      (node (ref "U1") (pin "43") (pinfunction "VDDCORE_43") (pintype "power_in"))
    )
    (net (code "49") (name "Net-(U2-BST)") (class "Default")
      (node (ref "C4") (pin "1") (pinfunction "1_1") (pintype "passive"))
      (node (ref "U2") (pin "5") (pinfunction "BST_5") (pintype "bidirectional"))
    )
    (net (code "50") (name "Net-(U2-EN{slash}SYNC)") (class "Default")
      (node (ref "R1") (pin "1") (pinfunction "1_1") (pintype "passive"))
      (node (ref "U2") (pin "6") (pinfunction "EN/SYNC_6") (pintype "bidirectional"))
    )
    (net (code "51") (name "Net-(U2-FB)") (class "Default")
      (node (ref "C5") (pin "1") (pinfunction "1_1") (pintype "passive"))
      (node (ref "R2") (pin "2") (pinfunction "2_2") (pintype "passive"))
      (node (ref "R3") (pin "1") (pinfunction "1_1") (pintype "passive"))
      (node (ref "U2") (pin "8") (pinfunction "FB_8") (pintype "bidirectional"))
    )
    (net (code "52") (name "Net-(U2-SW)") (class "Default")
      (node (ref "C4") (pin "2") (pinfunction "2_2") (pintype "passive"))
      (node (ref "L1") (pin "1") (pinfunction "1_1") (pintype "passive"))
      (node (ref "U2") (pin "3") (pinfunction "SW_3") (pintype "bidirectional"))
    )
    (net (code "53") (name "Net-(U2-VCC)") (class "Default")
      (node (ref "C3") (pin "2") (pinfunction "2_2") (pintype "passive"))
      (node (ref "U2") (pin "7") (pinfunction "VCC_7") (pintype "bidirectional"))
    )
    (net (code "54") (name "Net-(U5-ILIM)") (class "Default")
      (node (ref "R7") (pin "1") (pinfunction "1_1") (pintype "passive"))
      (node (ref "U5") (pin "4") (pinfunction "ILIM_4") (pintype "input"))
    )
    (net (code "55") (name "Net-(U5-OUT1)") (class "Default")
      (node (ref "J2") (pin "2") (pinfunction "2_2") (pintype "passive"))
      (node (ref "U5") (pin "6") (pinfunction "OUT1_6") (pintype "output"))
    )
    (net (code "56") (name "Net-(U5-OUT2)") (class "Default")
      (node (ref "J2") (pin "1") (pinfunction "1_1") (pintype "passive"))
      (node (ref "U5") (pin "8") (pinfunction "OUT2_8") (pintype "output"))
    )
    (net (code "57") (name "Net-(U6-ILIM)") (class "Default")
      (node (ref "R8") (pin "1") (pinfunction "1_1") (pintype "passive"))
      (node (ref "U6") (pin "4") (pinfunction "ILIM_4") (pintype "input"))
    )
    (net (code "58") (name "Net-(U6-OUT1)") (class "Default")
      (node (ref "J3") (pin "2") (pinfunction "2_2") (pintype "passive"))
      (node (ref "U6") (pin "6") (pinfunction "OUT1_6") (pintype "output"))
    )
    (net (code "59") (name "Net-(U6-OUT2)") (class "Default")
      (node (ref "J3") (pin "1") (pinfunction "1_1") (pintype "passive"))
      (node (ref "U6") (pin "8") (pinfunction "OUT2_8") (pintype "output"))
    )
    (net (code "60") (name "Net-(U7-B2)") (class "Default")
      (node (ref "J8") (pin "1") (pinfunction "1_1") (pintype "passive"))
      (node (ref "U7") (pin "12") (pinfunction "B2_12") (pintype "bidirectional"))
    )
    (net (code "61") (name "Net-(U7-B3)") (class "Default")
      (node (ref "J9") (pin "1") (pinfunction "1_1") (pintype "passive"))
      (node (ref "U7") (pin "11") (pinfunction "B3_11") (pintype "bidirectional"))
    )
    (net (code "62") (name "Net-(U7-B4)") (class "Default")
      (node (ref "J10") (pin "1") (pinfunction "1_1") (pintype "passive"))
      (node (ref "U7") (pin "10") (pinfunction "B4_10") (pintype "bidirectional"))
    )
    (net (code "63") (name "RX") (class "Default")
      (node (ref "J17") (pin "P$3") (pinfunction "3_P$3") (pintype "passive"))
      (node (ref "U1") (pin "20") (pinfunction "PB11_20") (pintype "bidirectional"))
    )
    (net (code "64") (name "SCL1") (class "Default")
      (node (ref "J15") (pin "21") (pinfunction "21_21") (pintype "passive"))
      (node (ref "J15") (pin "22") (pinfunction "22_22") (pintype "passive"))
      (node (ref "J6") (pin "1") (pinfunction "1_1") (pintype "passive"))
      (node (ref "R13") (pin "2") (pinfunction "2_2") (pintype "passive"))
      (node (ref "U1") (pin "26") (pinfunction "PA17_26") (pintype "bidirectional"))
    )
    (net (code "65") (name "SCL2") (class "Default")
      (node (ref "J16") (pin "P$2") (pinfunction "2_P$2") (pintype "passive"))
      (node (ref "R15") (pin "2") (pinfunction "2_2") (pintype "passive"))
      (node (ref "U1") (pin "22") (pinfunction "PA13_22") (pintype "bidirectional"))
      (node (ref "U9") (pin "13") (pinfunction "AP_SCL/AP_SCLK_13") (pintype "input"))
    )
    (net (code "66") (name "SDA1") (class "Default")
      (node (ref "J15") (pin "23") (pinfunction "23_23") (pintype "passive"))
      (node (ref "J15") (pin "24") (pinfunction "24_24") (pintype "passive"))
      (node (ref "J6") (pin "2") (pinfunction "2_2") (pintype "passive"))
      (node (ref "R14") (pin "2") (pinfunction "2_2") (pintype "passive"))
      (node (ref "U1") (pin "25") (pinfunction "PA16_25") (pintype "bidirectional"))
    )
    (net (code "67") (name "SDA2") (class "Default")
      (node (ref "J16") (pin "P$3") (pinfunction "3_P$3") (pintype "passive"))
      (node (ref "R16") (pin "2") (pinfunction "2_2") (pintype "passive"))
      (node (ref "U1") (pin "21") (pinfunction "PA12_21") (pintype "bidirectional"))
      (node (ref "U9") (pin "14") (pinfunction "AP_SDA/AP_SDIO/AP_SDI_14") (pintype "bidirectional"))
    )
    (net (code "68") (name "SERVO1") (class "Default")
      (node (ref "J12") (pin "3") (pinfunction "3_3") (pintype "passive"))
      (node (ref "U1") (pin "1") (pinfunction "PA00_1") (pintype "bidirectional"))
    )
    (net (code "69") (name "SERVO2") (class "Default")
      (node (ref "J12") (pin "6") (pinfunction "6_6") (pintype "passive"))
      (node (ref "U1") (pin "2") (pinfunction "PA01_2") (pintype "bidirectional"))
    )
    (net (code "70") (name "SERVO3") (class "Default")
      (node (ref "J12") (pin "9") (pinfunction "9_9") (pintype "passive"))
      (node (ref "U1") (pin "13") (pinfunction "PA08_13") (pintype "bidirectional"))
    )
    (net (code "71") (name "SERVO4") (class "Default")
      (node (ref "J12") (pin "12") (pinfunction "12_12") (pintype "passive"))
      (node (ref "U1") (pin "14") (pinfunction "PA09_14") (pintype "bidirectional"))
    )
    (net (code "72") (name "SONAR1ECHO") (class "Default")
      (node (ref "U1") (pin "41") (pinfunction "PA28_41") (pintype "bidirectional"))
      (node (ref "U7") (pin "5") (pinfunction "A4_5") (pintype "bidirectional"))
    )
    (net (code "73") (name "SONAR1TRIG") (class "Default")
      (node (ref "J10") (pin "2") (pinfunction "2_2") (pintype "passive"))
      (node (ref "U1") (pin "39") (pinfunction "PA27_39") (pintype "bidirectional"))
    )
    (net (code "74") (name "SONAR2ECHO") (class "Default")
      (node (ref "U1") (pin "47") (pinfunction "PB02_47") (pintype "bidirectional"))
      (node (ref "U7") (pin "4") (pinfunction "A3_4") (pintype "bidirectional"))
    )
    (net (code "75") (name "SONAR2TRIG") (class "Default")
      (node (ref "J9") (pin "2") (pinfunction "2_2") (pintype "passive"))
      (node (ref "U1") (pin "38") (pinfunction "PB23_38") (pintype "bidirectional"))
    )
    (net (code "76") (name "SONAR3ECHO") (class "Default")
      (node (ref "U1") (pin "48") (pinfunction "PB03_48") (pintype "bidirectional"))
      (node (ref "U7") (pin "3") (pinfunction "A2_3") (pintype "bidirectional"))
    )
    (net (code "77") (name "SONAR3TRIG") (class "Default")
      (node (ref "J8") (pin "2") (pinfunction "2_2") (pintype "passive"))
      (node (ref "U1") (pin "37") (pinfunction "PB22_37") (pintype "bidirectional"))
    )
    (net (code "78") (name "SWCLK") (class "Default")
      (node (ref "R11") (pin "2") (pinfunction "2_2") (pintype "passive"))
      (node (ref "TP2") (pin "TP") (pinfunction "TP_TP") (pintype "input"))
      (node (ref "U1") (pin "45") (pinfunction "PA30_45") (pintype "bidirectional"))
    )
    (net (code "79") (name "SWDIO") (class "Default")
      (node (ref "TP3") (pin "TP") (pinfunction "TP_TP") (pintype "input"))
      (node (ref "U1") (pin "46") (pinfunction "PA31_46") (pintype "bidirectional"))
    )
    (net (code "80") (name "TX") (class "Default")
      (node (ref "J17") (pin "P$2") (pinfunction "2_P$2") (pintype "passive"))
      (node (ref "U1") (pin "19") (pinfunction "PB10_19") (pintype "bidirectional"))
    )
    (net (code "81") (name "VSENSE") (class "Default")
      (node (ref "R5") (pin "1") (pinfunction "1_1") (pintype "passive"))
      (node (ref "R6") (pin "1") (pinfunction "1_1") (pintype "passive"))
      (node (ref "U1") (pin "12") (pinfunction "PA07_12") (pintype "bidirectional"))
    )
    (net (code "82") (name "unconnected-(J15-Pad1)") (class "Default")
      (node (ref "J15") (pin "1") (pinfunction "1_1") (pintype "passive"))
    )
    (net (code "83") (name "unconnected-(J15-Pad5)") (class "Default")
      (node (ref "J15") (pin "5") (pinfunction "5_5") (pintype "passive"))
    )
    (net (code "84") (name "unconnected-(J17-4-PadP$4)") (class "Default")
      (node (ref "J17") (pin "P$4") (pinfunction "4_P$4") (pintype "passive"))
    )
    (net (code "85") (name "unconnected-(J17-5-PadP$5)") (class "Default")
      (node (ref "J17") (pin "P$5") (pinfunction "5_P$5") (pintype "passive"))
    )
    (net (code "86") (name "unconnected-(U1-PA03-Pad4)") (class "Default")
      (node (ref "U1") (pin "4") (pinfunction "PA03_4") (pintype "bidirectional"))
    )
    (net (code "87") (name "unconnected-(U1-PA11-Pad16)") (class "Default")
      (node (ref "U1") (pin "16") (pinfunction "PA11_16") (pintype "bidirectional"))
    )
    (net (code "88") (name "unconnected-(U7-A1-Pad2)") (class "Default")
      (node (ref "U7") (pin "2") (pinfunction "A1_2") (pintype "bidirectional"))
    )
    (net (code "89") (name "unconnected-(U7-B1-Pad13)") (class "Default")
      (node (ref "U7") (pin "13") (pinfunction "B1_13") (pintype "bidirectional"))
    )
    (net (code "90") (name "unconnected-(U7-NC-Pad9)") (class "Default")
      (node (ref "U7") (pin "9") (pinfunction "NC_9") (pintype "no_connect"))
    )
    (net (code "91") (name "unconnected-(U7-NC_2-Pad6)") (class "Default")
      (node (ref "U7") (pin "6") (pinfunction "NC_2_6") (pintype "no_connect"))
    )
    (net (code "92") (name "unconnected-(U9-INT1{slash}INT-Pad4)") (class "Default")
      (node (ref "U9") (pin "4") (pinfunction "INT1/INT_4") (pintype "output"))
    )
    (net (code "93") (name "unconnected-(U9-RESV_1-Pad2)") (class "Default")
      (node (ref "U9") (pin "2") (pinfunction "RESV_1_2") (pintype "bidirectional"))
    )
    (net (code "94") (name "unconnected-(U9-RESV_2-Pad3)") (class "Default")
      (node (ref "U9") (pin "3") (pinfunction "RESV_2_3") (pintype "bidirectional"))
    )
    (net (code "95") (name "unconnected-(U9-RESV_4-Pad10)") (class "Default")
      (node (ref "U9") (pin "10") (pinfunction "RESV_4_10") (pintype "bidirectional"))
    )
    (net (code "96") (name "unconnected-(U9-RESV_5-Pad11)") (class "Default")
      (node (ref "U9") (pin "11") (pinfunction "RESV_5_11") (pintype "bidirectional"))
    )
    (net (code "97") (name "unconnected-(USB1-ID-Pad4)") (class "Default")
      (node (ref "USB1") (pin "4") (pinfunction "ID_4") (pintype "bidirectional"))
    )
    (net (code "98") (name "unconnected-(USB1-VCC-Pad1)") (class "Default")
      (node (ref "USB1") (pin "1") (pinfunction "VCC_1") (pintype "bidirectional"))
    )
    (net (code "99") (name "~{RESET}") (class "Default")
      (node (ref "C14") (pin "1") (pinfunction "1_1") (pintype "passive"))
      (node (ref "J14") (pin "1") (pinfunction "1_1") (pintype "passive"))
      (node (ref "J14") (pin "2") (pinfunction "2_2") (pintype "passive"))
      (node (ref "R10") (pin "2") (pinfunction "2_2") (pintype "passive"))
      (node (ref "TP1") (pin "TP") (pinfunction "TP_TP") (pintype "input"))
      (node (ref "U1") (pin "40") (pinfunction "RSTN_40") (pintype "bidirectional"))
    )
  )
)
